# Sensors.net
KiCad netlist of a schematic drawn in Altium Designer
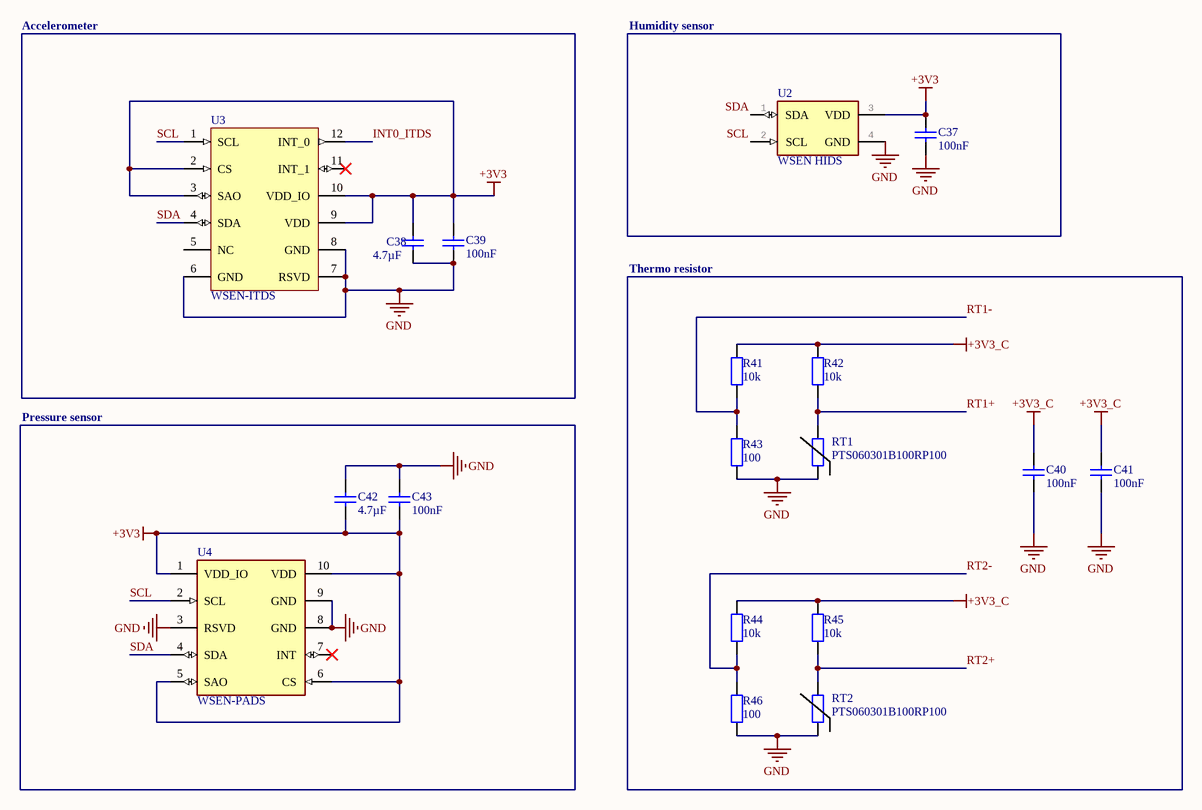
[diagram p0: Sensors.SchDoc]

(export (version "E")
  (design (tool "Eeschema 10.0.6"))
  (components
    (comp (ref "C37")
      (value "100nF")
      (footprint "WCAP-CSGP_0603_L1.6W0.8H0.8_Reflow")
      (description "WCAP-CSGP Multilayer Ceramic Chip Capacitor, General Purpose, size 0603, X7R, 100nF, 25VDC")
      (fields
        (field (name "MANUFACTURER") "Wurth Elektronik")
        (field (name "MANUFACTURER PART NUMBER") "885012206071")
      )
      (libsource (lib "LEEM UPM") (part "885012209047R"))
    )
    (comp (ref "C38")
      (value "4.7µF")
      (footprint "WCAP-CSGP_0603_L1.6W0.8H0.8_Reflow")
      (description "WCAP-CSGP Multilayer Ceramic Chip Capacitor, General Purpose, size 0603, X5R, 4.7uF, 10VDC")
      (fields
        (field (name "MANUFACTURER PART NUMBER") "885012106012")
        (field (name "MANUFACTURER") "Wurth Elektronik")
      )
      (libsource (lib "LEEM UPM") (part "885012209047R"))
    )
    (comp (ref "C39")
      (value "100nF")
      (footprint "WCAP-CSGP_0603_L1.6W0.8H0.8_Reflow")
      (description "WCAP-CSGP Multilayer Ceramic Chip Capacitor, General Purpose, size 0603, X7R, 100nF, 25VDC")
      (fields
        (field (name "MANUFACTURER") "Wurth Elektronik")
        (field (name "MANUFACTURER PART NUMBER") "885012206071")
      )
      (libsource (lib "LEEM UPM") (part "885012209047R"))
    )
    (comp (ref "C40")
      (value "100nF")
      (footprint "WCAP-CSGP_0603_L1.6W0.8H0.8_Reflow")
      (description "WCAP-CSGP Multilayer Ceramic Chip Capacitor, General Purpose, size 0603, X7R, 100nF, 10VDC")
      (fields
        (field (name "MANUFACTURER PART NUMBER") "885012206020")
        (field (name "MANUFACTURER") "Wurth Elektronik")
      )
      (libsource (lib "LEEM UPM") (part "885012209047R"))
    )
    (comp (ref "C41")
      (value "100nF")
      (footprint "WCAP-CSGP_0603_L1.6W0.8H0.8_Reflow")
      (description "WCAP-CSGP Multilayer Ceramic Chip Capacitor, General Purpose, size 0603, X7R, 100nF, 10VDC")
      (fields
        (field (name "MANUFACTURER PART NUMBER") "885012206020")
        (field (name "MANUFACTURER") "Wurth Elektronik")
      )
      (libsource (lib "LEEM UPM") (part "885012209047R"))
    )
    (comp (ref "C42")
      (value "4.7µF")
      (footprint "WCAP-CSGP_0603_L1.6W0.8H0.8_Reflow")
      (description "WCAP-CSGP Multilayer Ceramic Chip Capacitor, General Purpose, size 0603, X5R, 4.7uF, 10VDC")
      (fields
        (field (name "MANUFACTURER PART NUMBER") "885012106012")
        (field (name "MANUFACTURER") "Wurth Elektronik")
      )
      (libsource (lib "LEEM UPM") (part "885012209047R"))
    )
    (comp (ref "C43")
      (value "100nF")
      (footprint "WCAP-CSGP_0603_L1.6W0.8H0.8_Reflow")
      (description "WCAP-CSGP Multilayer Ceramic Chip Capacitor, General Purpose, size 0603, X7R, 100nF, 25VDC")
      (fields
        (field (name "MANUFACTURER") "Wurth Elektronik")
        (field (name "MANUFACTURER PART NUMBER") "885012206071")
      )
      (libsource (lib "LEEM UPM") (part "885012209047R"))
    )
    (comp (ref "R41")
      (value "10k")
      (footprint "WRIS-RSKS_0603_Reflow")
      (description "WRIS-RSKS Thick Film Resistor, size 0603, 10000Ohm, 100mW")
      (fields
        (field (name "MANUFACTURER") "Wurth Elektronik")
        (field (name "MANUFACTURER PART NUMBER") "560112116005")
      )
      (libsource (lib "LEEM UPM") (part "560112140010"))
    )
    (comp (ref "R42")
      (value "10k")
      (footprint "WRIS-RSKS_0603_Reflow")
      (description "WRIS-RSKS Thick Film Resistor, size 0603, 10000Ohm, 100mW")
      (fields
        (field (name "MANUFACTURER") "Wurth Elektronik")
        (field (name "MANUFACTURER PART NUMBER") "560112116005")
      )
      (libsource (lib "LEEM UPM") (part "560112140010"))
    )
    (comp (ref "R43")
      (value "100")
      (footprint "WRIS-RSKS_0603_Reflow")
      (description "WRIS-RSKS Thick Film Resistor, size 0603, 100Ohm, 100mW")
      (fields
        (field (name "MANUFACTURER") "Wurth Elektronik")
        (field (name "MANUFACTURER PART NUMBER") "560112116009")
      )
      (libsource (lib "LEEM UPM") (part "560112140010"))
    )
    (comp (ref "R44")
      (value "10k")
      (footprint "WRIS-RSKS_0603_Reflow")
      (description "WRIS-RSKS Thick Film Resistor, size 0603, 10000Ohm, 100mW")
      (fields
        (field (name "MANUFACTURER") "Wurth Elektronik")
        (field (name "MANUFACTURER PART NUMBER") "560112116005")
      )
      (libsource (lib "LEEM UPM") (part "560112140010"))
    )
    (comp (ref "R45")
      (value "10k")
      (footprint "WRIS-RSKS_0603_Reflow")
      (description "WRIS-RSKS Thick Film Resistor, size 0603, 10000Ohm, 100mW")
      (fields
        (field (name "MANUFACTURER") "Wurth Elektronik")
        (field (name "MANUFACTURER PART NUMBER") "560112116005")
      )
      (libsource (lib "LEEM UPM") (part "560112140010"))
    )
    (comp (ref "R46")
      (value "100")
      (footprint "WRIS-RSKS_0603_Reflow")
      (description "WRIS-RSKS Thick Film Resistor, size 0603, 100Ohm, 100mW")
      (fields
        (field (name "MANUFACTURER") "Wurth Elektronik")
        (field (name "MANUFACTURER PART NUMBER") "560112116009")
      )
      (libsource (lib "LEEM UPM") (part "560112140010"))
    )
    (comp (ref "RT1")
      (value "PTS060301B100RP100")
      (footprint "PTS060301B100RP100-Footprint-1")
      (description "RTD Platinum Sensor, 100ohm, Rectangular, Surface Mount")
      (libsource (lib "LEEM UPM") (part "PTS060301B100RP100"))
    )
    (comp (ref "RT2")
      (value "PTS060301B100RP100")
      (footprint "PTS060301B100RP100-Footprint-1")
      (description "RTD Platinum Sensor, 100ohm, Rectangular, Surface Mount")
      (libsource (lib "LEEM UPM") (part "PTS060301B100RP100"))
    )
    (comp (ref "U2")
      (value "WSEN HIDS")
      (footprint "WSEN HIDS-Footprint-1")
      (description "Wsen-hids/ Humidity, temperature Sensor")
      (libsource (lib "LEEM UPM") (part "WSEN HIDS"))
    )
    (comp (ref "U3")
      (value "WSEN-ITDS")
      (footprint "WSEN-ITDS-Footprint-1")
      (description "IMU (3 axis)")
      (libsource (lib "LEEM UPM") (part "WSEN-ITDS"))
    )
    (comp (ref "U4")
      (value "WSEN-PADS")
      (footprint "WSEN-PADS-Footprint-1")
      (description "Piezoresistive Sensor, Absolute pressure sensor")
      (libsource (lib "LEEM UPM") (part "WSEN-PADS"))
    )
  )
  (nets
    (net (code "1") (name "+3V3") (class "Default")
      (node (ref "C37") (pin "2") (pinfunction "2_2") (pintype "passive"))
      (node (ref "C38") (pin "1") (pinfunction "1_1") (pintype "passive"))
      (node (ref "C39") (pin "2") (pinfunction "2_2") (pintype "passive"))
      (node (ref "C42") (pin "2") (pinfunction "2_2") (pintype "passive"))
      (node (ref "C43") (pin "1") (pinfunction "1_1") (pintype "passive"))
      (node (ref "U2") (pin "3") (pinfunction "VDD_3") (pintype "power_in"))
      (node (ref "U3") (pin "10") (pinfunction "VDD_IO_10") (pintype "power_in"))
      (node (ref "U3") (pin "2") (pinfunction "CS_2") (pintype "input"))
      (node (ref "U3") (pin "3") (pinfunction "SAO_3") (pintype "bidirectional"))
      (node (ref "U3") (pin "9") (pinfunction "VDD_9") (pintype "power_in"))
      (node (ref "U4") (pin "1") (pinfunction "VDD_IO_1") (pintype "power_in"))
      (node (ref "U4") (pin "10") (pinfunction "VDD_10") (pintype "power_in"))
      (node (ref "U4") (pin "5") (pinfunction "SAO_5") (pintype "bidirectional"))
      (node (ref "U4") (pin "6") (pinfunction "CS_6") (pintype "input"))
    )
    (net (code "2") (name "+3V3_C") (class "Default")
      (node (ref "C40") (pin "2") (pinfunction "2_2") (pintype "passive"))
      (node (ref "C41") (pin "2") (pinfunction "2_2") (pintype "passive"))
      (node (ref "R41") (pin "2") (pinfunction "2_2") (pintype "passive"))
      (node (ref "R42") (pin "2") (pinfunction "2_2") (pintype "passive"))
      (node (ref "R44") (pin "2") (pinfunction "2_2") (pintype "passive"))
      (node (ref "R45") (pin "2") (pinfunction "2_2") (pintype "passive"))
    )
    (net (code "3") (name "/INT0_ITDS") (class "Default")
      (node (ref "U3") (pin "12") (pinfunction "INT_0_12") (pintype "output"))
    )
    (net (code "4") (name "/RT1+") (class "Default")
      (node (ref "R42") (pin "1") (pinfunction "1_1") (pintype "passive"))
      (node (ref "RT1") (pin "2") (pinfunction "2_2") (pintype "passive"))
    )
    (net (code "5") (name "/RT1-") (class "Default")
      (node (ref "R41") (pin "1") (pinfunction "1_1") (pintype "passive"))
      (node (ref "R43") (pin "2") (pinfunction "2_2") (pintype "passive"))
    )
    (net (code "6") (name "/RT2+") (class "Default")
      (node (ref "R45") (pin "1") (pinfunction "1_1") (pintype "passive"))
      (node (ref "RT2") (pin "2") (pinfunction "2_2") (pintype "passive"))
    )
    (net (code "7") (name "/RT2-") (class "Default")
      (node (ref "R44") (pin "1") (pinfunction "1_1") (pintype "passive"))
      (node (ref "R46") (pin "2") (pinfunction "2_2") (pintype "passive"))
    )
    (net (code "8") (name "/SCL") (class "Default")
      (node (ref "U2") (pin "2") (pinfunction "SCL_2") (pintype "input"))
      (node (ref "U3") (pin "1") (pinfunction "SCL_1") (pintype "input"))
      (node (ref "U4") (pin "2") (pinfunction "SCL_2") (pintype "input"))
    )
    (net (code "9") (name "/SDA") (class "Default")
      (node (ref "U2") (pin "1") (pinfunction "SDA_1") (pintype "bidirectional"))
      (node (ref "U3") (pin "4") (pinfunction "SDA_4") (pintype "bidirectional"))
      (node (ref "U4") (pin "4") (pinfunction "SDA_4") (pintype "bidirectional"))
    )
    (net (code "10") (name "GND") (class "Default")
      (node (ref "C37") (pin "1") (pinfunction "1_1") (pintype "passive"))
      (node (ref "C38") (pin "2") (pinfunction "2_2") (pintype "passive"))
      (node (ref "C39") (pin "1") (pinfunction "1_1") (pintype "passive"))
      (node (ref "C40") (pin "1") (pinfunction "1_1") (pintype "passive"))
      (node (ref "C41") (pin "1") (pinfunction "1_1") (pintype "passive"))
      (node (ref "C42") (pin "1") (pinfunction "1_1") (pintype "passive"))
      (node (ref "C43") (pin "2") (pinfunction "2_2") (pintype "passive"))
      (node (ref "R43") (pin "1") (pinfunction "1_1") (pintype "passive"))
      (node (ref "R46") (pin "1") (pinfunction "1_1") (pintype "passive"))
      (node (ref "RT1") (pin "1") (pinfunction "1_1") (pintype "passive"))
      (node (ref "RT2") (pin "1") (pinfunction "1_1") (pintype "passive"))
      (node (ref "U2") (pin "4") (pinfunction "GND_4") (pintype "power_in"))
      (node (ref "U3") (pin "6") (pinfunction "GND_6") (pintype "power_in"))
      (node (ref "U3") (pin "7") (pinfunction "RSVD_7") (pintype "passive"))
      (node (ref "U3") (pin "8") (pinfunction "GND_8") (pintype "power_in"))
      (node (ref "U4") (pin "3") (pinfunction "RSVD_3") (pintype "passive"))
      (node (ref "U4") (pin "8") (pinfunction "GND_8") (pintype "power_in"))
      (node (ref "U4") (pin "9") (pinfunction "GND_9") (pintype "power_in"))
    )
    (net (code "11") (name "unconnected-(U3-INT_1-Pad11)") (class "Default")
      (node (ref "U3") (pin "11") (pinfunction "INT_1_11") (pintype "bidirectional+no_connect"))
    )
    (net (code "12") (name "unconnected-(U3-NC-Pad5)") (class "Default")
      (node (ref "U3") (pin "5") (pinfunction "NC_5") (pintype "passive"))
    )
    (net (code "13") (name "unconnected-(U4-INT-Pad7)") (class "Default")
      (node (ref "U4") (pin "7") (pinfunction "INT_7") (pintype "bidirectional+no_connect"))
    )
  )
)
